# honeybee.net
KiCad netlist of a schematic drawn in EAGLE
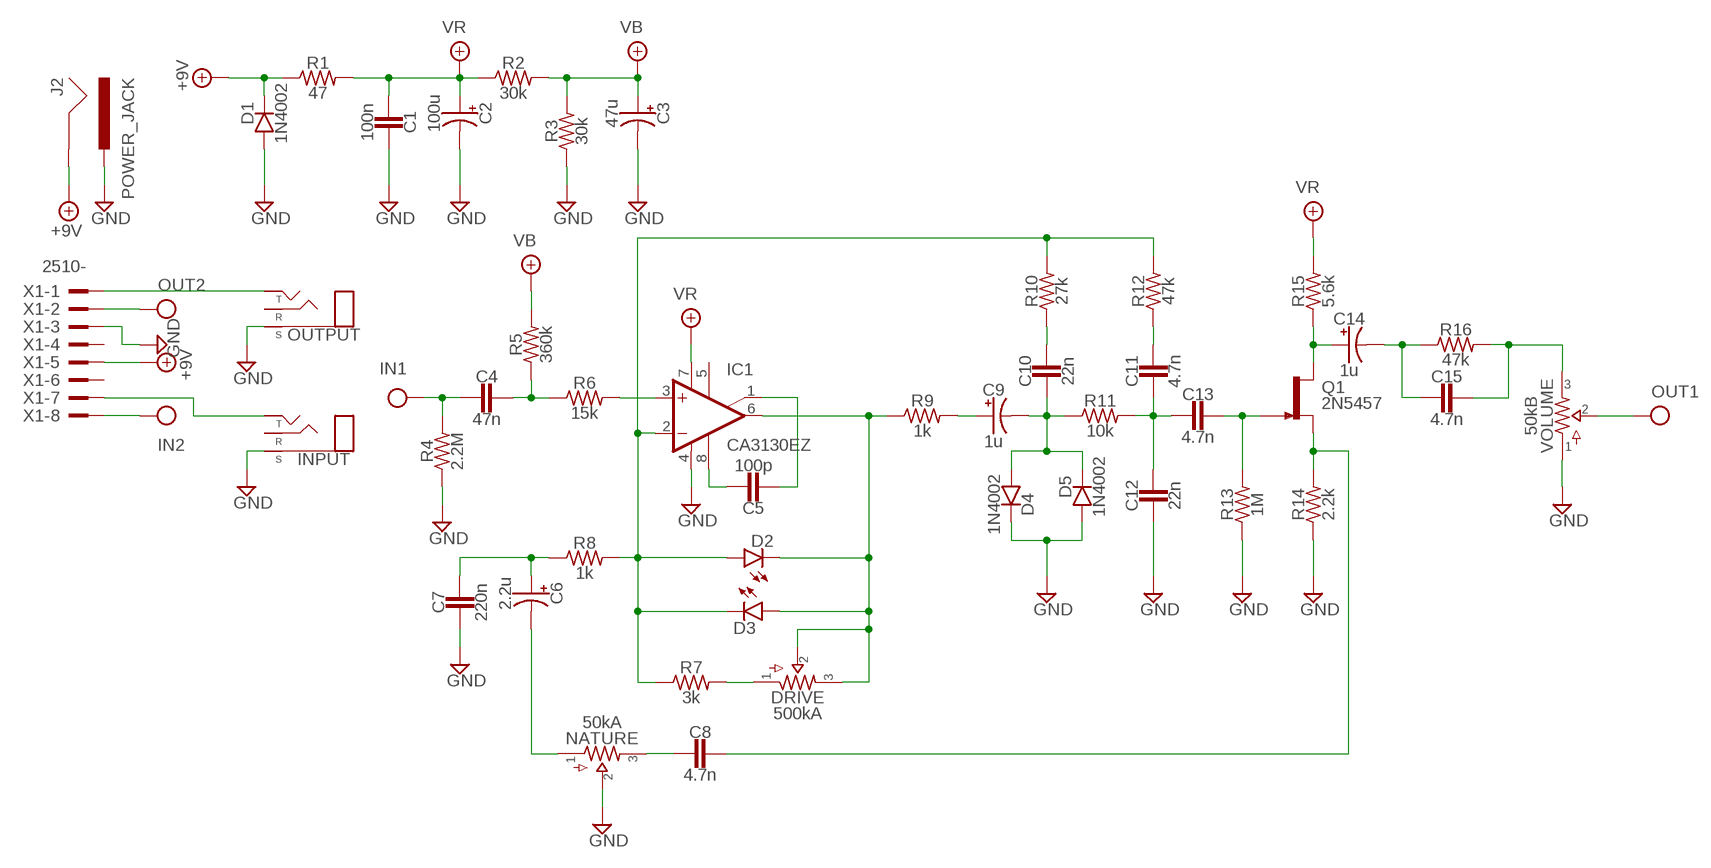
[diagram p0: schematic, sheet 1]

(export (version "E")
  (design (tool "Eeschema 10.0.6"))
  (components
    (comp (ref "C1")
      (value "100n")
      (footprint "eagle-import:050X030_025_2")
      (libsource (lib "eagle-import") (part "CER/FILM2"))
    )
    (comp (ref "C2")
      (value "100u")
      (footprint "eagle-import:040_020")
      (libsource (lib "eagle-import") (part "0400"))
    )
    (comp (ref "C3")
      (value "47u")
      (footprint "eagle-import:040_020")
      (libsource (lib "eagle-import") (part "0400"))
    )
    (comp (ref "C4")
      (value "47n")
      (footprint "eagle-import:BOX_SMALL")
      (libsource (lib "eagle-import") (part "CER/FILMBOX.1"))
    )
    (comp (ref "C5")
      (value "100p")
      (footprint "eagle-import:050X030_025_2")
      (libsource (lib "eagle-import") (part "CER/FILM2"))
    )
    (comp (ref "C6")
      (value "2.2u")
      (footprint "eagle-import:050_020")
      (libsource (lib "eagle-import") (part "0500"))
    )
    (comp (ref "C7")
      (value "220n")
      (footprint "eagle-import:BOX_SMALL")
      (libsource (lib "eagle-import") (part "CER/FILMBOX.1"))
    )
    (comp (ref "C8")
      (value "4.7n")
      (footprint "eagle-import:BOX_SMALL")
      (libsource (lib "eagle-import") (part "CER/FILMBOX.1"))
    )
    (comp (ref "C9")
      (value "1u")
      (footprint "eagle-import:040_020")
      (libsource (lib "eagle-import") (part "0400"))
    )
    (comp (ref "C10")
      (value "22n")
      (footprint "eagle-import:BOX_SMALL")
      (libsource (lib "eagle-import") (part "CER/FILMBOX.1"))
    )
    (comp (ref "C11")
      (value "4.7n")
      (footprint "eagle-import:BOX_SMALL")
      (libsource (lib "eagle-import") (part "CER/FILMBOX.1"))
    )
    (comp (ref "C12")
      (value "22n")
      (footprint "eagle-import:BOX_SMALL")
      (libsource (lib "eagle-import") (part "CER/FILMBOX.1"))
    )
    (comp (ref "C13")
      (value "4.7n")
      (footprint "eagle-import:BOX_SMALL")
      (libsource (lib "eagle-import") (part "CER/FILMBOX.1"))
    )
    (comp (ref "C14")
      (value "1u")
      (footprint "eagle-import:040_020")
      (libsource (lib "eagle-import") (part "0400"))
    )
    (comp (ref "C15")
      (value "4.7n")
      (footprint "eagle-import:BOX_SMALL")
      (libsource (lib "eagle-import") (part "CER/FILMBOX.1"))
    )
    (comp (ref "D1")
      (value "1N4002")
      (footprint "eagle-import:DO41-2")
      (libsource (lib "eagle-import") (part "DO41.2"))
    )
    (comp (ref "D2")
      (value "LED")
      (footprint "eagle-import:3MM_D")
      (libsource (lib "eagle-import") (part "LED"))
    )
    (comp (ref "D3")
      (value "LED")
      (footprint "eagle-import:3MM_D")
      (libsource (lib "eagle-import") (part "LED"))
    )
    (comp (ref "D4")
      (value "1N4002")
      (footprint "eagle-import:DO41-2")
      (libsource (lib "eagle-import") (part "DO41.2"))
    )
    (comp (ref "D5")
      (value "1N4002")
      (footprint "eagle-import:DO41-2")
      (libsource (lib "eagle-import") (part "DO41.2"))
    )
    (comp (ref "DRIVE")
      (value "500kA")
      (footprint "eagle-import:16MM")
      (libsource (lib "eagle-import") (part "POTS16MM"))
    )
    (comp (ref "IC1")
      (value "CA3130EZ")
      (footprint "eagle-import:DIL08")
      (libsource (lib "eagle-import") (part "CA3130N"))
    )
    (comp (ref "INPUT")
      (value "STEREONMJ")
      (footprint "eagle-import:NMJ6HCD2")
      (libsource (lib "eagle-import") (part "STEREONMJ"))
    )
    (comp (ref "J2")
      (value "POWER_JACK")
      (footprint "eagle-import:POWER_JACK_PTH")
      (libsource (lib "eagle-import") (part "POWER_JACK"))
    )
    (comp (ref "NATURE")
      (value "50kA")
      (footprint "eagle-import:16MM")
      (libsource (lib "eagle-import") (part "POTS16MM"))
    )
    (comp (ref "OUTPUT")
      (value "STEREONMJ")
      (footprint "eagle-import:NMJ6HCD2")
      (libsource (lib "eagle-import") (part "STEREONMJ"))
    )
    (comp (ref "Q1")
      (value "2N5457")
      (footprint "eagle-import:TO92-")
      (libsource (lib "eagle-import") (part "2N5457"))
    )
    (comp (ref "R1")
      (value "47")
      (footprint "eagle-import:R0207_3")
      (libsource (lib "eagle-import") (part "R_.3B"))
    )
    (comp (ref "R2")
      (value "30k")
      (footprint "eagle-import:R0207_3")
      (libsource (lib "eagle-import") (part "R_.3B"))
    )
    (comp (ref "R3")
      (value "30k")
      (footprint "eagle-import:R0207_3")
      (libsource (lib "eagle-import") (part "R_.3B"))
    )
    (comp (ref "R4")
      (value "2.2M")
      (footprint "eagle-import:R0207_3")
      (libsource (lib "eagle-import") (part "R_.3B"))
    )
    (comp (ref "R5")
      (value "360k")
      (footprint "eagle-import:R0207_3")
      (libsource (lib "eagle-import") (part "R_.3B"))
    )
    (comp (ref "R6")
      (value "15k")
      (footprint "eagle-import:R0207_3")
      (libsource (lib "eagle-import") (part "R_.3B"))
    )
    (comp (ref "R7")
      (value "3k")
      (footprint "eagle-import:R0207_3")
      (libsource (lib "eagle-import") (part "R_.3B"))
    )
    (comp (ref "R8")
      (value "1k")
      (footprint "eagle-import:R0207_3")
      (libsource (lib "eagle-import") (part "R_.3B"))
    )
    (comp (ref "R9")
      (value "1k")
      (footprint "eagle-import:R0207_3")
      (libsource (lib "eagle-import") (part "R_.3B"))
    )
    (comp (ref "R10")
      (value "27k")
      (footprint "eagle-import:R0207_3")
      (libsource (lib "eagle-import") (part "R_.3B"))
    )
    (comp (ref "R11")
      (value "10k")
      (footprint "eagle-import:R0207_3")
      (libsource (lib "eagle-import") (part "R_.3B"))
    )
    (comp (ref "R12")
      (value "47k")
      (footprint "eagle-import:R0207_3")
      (libsource (lib "eagle-import") (part "R_.3B"))
    )
    (comp (ref "R13")
      (value "1M")
      (footprint "eagle-import:R0207_3")
      (libsource (lib "eagle-import") (part "R_.3B"))
    )
    (comp (ref "R14")
      (value "2.2k")
      (footprint "eagle-import:R0207_3")
      (libsource (lib "eagle-import") (part "R_.3B"))
    )
    (comp (ref "R15")
      (value "5.6k")
      (footprint "eagle-import:R0207_3")
      (libsource (lib "eagle-import") (part "R_.3B"))
    )
    (comp (ref "R16")
      (value "47k")
      (footprint "eagle-import:R0207_3")
      (libsource (lib "eagle-import") (part "R_.3B"))
    )
    (comp (ref "VOLUME")
      (value "50kB")
      (footprint "eagle-import:16MM")
      (libsource (lib "eagle-import") (part "POTS16MM"))
    )
    (comp (ref "X1")
      (value "2510-")
      (footprint "eagle-import:PAK100_2500-10")
      (fields (field (name "MF") "3M") (field (name "MPN") "2510-6002UB"))
      (libsource (lib "eagle-import") (part "2510-"))
    )
  )
  (nets
    (net (code "1") (name "+9V") (class "Default")
      (node (ref "D1") (pin "C") (pinfunction "C_C") (pintype "passive"))
      (node (ref "J2") (pin "GND") (pinfunction "GND_GND") (pintype "bidirectional"))
      (node (ref "R1") (pin "1") (pinfunction "1_1") (pintype "passive"))
      (node (ref "X1") (pin "5") (pinfunction "KL_5") (pintype "passive"))
    )
    (net (code "2") (name "GND") (class "Default")
      (node (ref "C1") (pin "1") (pinfunction "1_1") (pintype "passive"))
      (node (ref "C12") (pin "2") (pinfunction "2_2") (pintype "passive"))
      (node (ref "C2") (pin "-") (pinfunction "-_-") (pintype "passive"))
      (node (ref "C3") (pin "-") (pinfunction "-_-") (pintype "passive"))
      (node (ref "C7") (pin "2") (pinfunction "2_2") (pintype "passive"))
      (node (ref "D1") (pin "A") (pinfunction "A_A") (pintype "passive"))
      (node (ref "D4") (pin "C") (pinfunction "C_C") (pintype "passive"))
      (node (ref "D5") (pin "A") (pinfunction "A_A") (pintype "passive"))
      (node (ref "IC1") (pin "4") (pinfunction "V-_4") (pintype "power_in"))
      (node (ref "INPUT") (pin "S") (pinfunction "S_S") (pintype "passive"))
      (node (ref "J2") (pin "PWR") (pinfunction "PWR_PWR") (pintype "bidirectional"))
      (node (ref "NATURE") (pin "2") (pinfunction "2_2") (pintype "passive"))
      (node (ref "OUTPUT") (pin "S") (pinfunction "S_S") (pintype "passive"))
      (node (ref "R13") (pin "1") (pinfunction "1_1") (pintype "passive"))
      (node (ref "R14") (pin "1") (pinfunction "1_1") (pintype "passive"))
      (node (ref "R3") (pin "1") (pinfunction "1_1") (pintype "passive"))
      (node (ref "R4") (pin "1") (pinfunction "1_1") (pintype "passive"))
      (node (ref "VOLUME") (pin "1") (pinfunction "1_1") (pintype "passive"))
      (node (ref "X1") (pin "3") (pinfunction "KL_3") (pintype "passive"))
    )
    (net (code "3") (name "IN") (class "Default")
      (node (ref "C4") (pin "2") (pinfunction "2_2") (pintype "passive"))
      (node (ref "R4") (pin "2") (pinfunction "2_2") (pintype "passive"))
      (node (ref "X1") (pin "8") (pinfunction "KL_8") (pintype "passive"))
    )
    (net (code "4") (name "Net-(C4-Pad1)") (class "Default")
      (node (ref "C4") (pin "1") (pinfunction "1_1") (pintype "passive"))
      (node (ref "R5") (pin "1") (pinfunction "1_1") (pintype "passive"))
      (node (ref "R6") (pin "1") (pinfunction "1_1") (pintype "passive"))
    )
    (net (code "5") (name "Net-(C6-Pad+)") (class "Default")
      (node (ref "C6") (pin "+") (pinfunction "+_+") (pintype "passive"))
      (node (ref "C7") (pin "1") (pinfunction "1_1") (pintype "passive"))
      (node (ref "R8") (pin "1") (pinfunction "1_1") (pintype "passive"))
    )
    (net (code "6") (name "Net-(C6-Pad-)") (class "Default")
      (node (ref "C6") (pin "-") (pinfunction "-_-") (pintype "passive"))
      (node (ref "NATURE") (pin "1") (pinfunction "1_1") (pintype "passive"))
    )
    (net (code "7") (name "Net-(C8-Pad2)") (class "Default")
      (node (ref "C8") (pin "2") (pinfunction "2_2") (pintype "passive"))
      (node (ref "NATURE") (pin "3") (pinfunction "3_3") (pintype "passive"))
    )
    (net (code "8") (name "Net-(C9-Pad+)") (class "Default")
      (node (ref "C9") (pin "+") (pinfunction "+_+") (pintype "passive"))
      (node (ref "R9") (pin "2") (pinfunction "2_2") (pintype "passive"))
    )
    (net (code "9") (name "Net-(C10-Pad1)") (class "Default")
      (node (ref "C10") (pin "1") (pinfunction "1_1") (pintype "passive"))
      (node (ref "R10") (pin "1") (pinfunction "1_1") (pintype "passive"))
    )
    (net (code "10") (name "Net-(C10-Pad2)") (class "Default")
      (node (ref "C10") (pin "2") (pinfunction "2_2") (pintype "passive"))
      (node (ref "C9") (pin "-") (pinfunction "-_-") (pintype "passive"))
      (node (ref "D4") (pin "A") (pinfunction "A_A") (pintype "passive"))
      (node (ref "D5") (pin "C") (pinfunction "C_C") (pintype "passive"))
      (node (ref "R11") (pin "1") (pinfunction "1_1") (pintype "passive"))
    )
    (net (code "11") (name "Net-(C11-Pad1)") (class "Default")
      (node (ref "C11") (pin "1") (pinfunction "1_1") (pintype "passive"))
      (node (ref "R12") (pin "1") (pinfunction "1_1") (pintype "passive"))
    )
    (net (code "12") (name "Net-(C11-Pad2)") (class "Default")
      (node (ref "C11") (pin "2") (pinfunction "2_2") (pintype "passive"))
      (node (ref "C12") (pin "1") (pinfunction "1_1") (pintype "passive"))
      (node (ref "C13") (pin "2") (pinfunction "2_2") (pintype "passive"))
      (node (ref "R11") (pin "2") (pinfunction "2_2") (pintype "passive"))
    )
    (net (code "13") (name "Net-(C14-Pad-)") (class "Default")
      (node (ref "C14") (pin "-") (pinfunction "-_-") (pintype "passive"))
      (node (ref "C15") (pin "2") (pinfunction "2_2") (pintype "passive"))
      (node (ref "R16") (pin "1") (pinfunction "1_1") (pintype "passive"))
    )
    (net (code "14") (name "Net-(C15-Pad1)") (class "Default")
      (node (ref "C15") (pin "1") (pinfunction "1_1") (pintype "passive"))
      (node (ref "R16") (pin "2") (pinfunction "2_2") (pintype "passive"))
      (node (ref "VOLUME") (pin "3") (pinfunction "3_3") (pintype "passive"))
    )
    (net (code "15") (name "Net-(D2-A)") (class "Default")
      (node (ref "D2") (pin "ANODE") (pinfunction "A_ANODE") (pintype "passive"))
      (node (ref "D3") (pin "P$1") (pinfunction "C_P$1") (pintype "passive"))
      (node (ref "IC1") (pin "2") (pinfunction "-IN_2") (pintype "input"))
      (node (ref "R10") (pin "2") (pinfunction "2_2") (pintype "passive"))
      (node (ref "R12") (pin "2") (pinfunction "2_2") (pintype "passive"))
      (node (ref "R7") (pin "1") (pinfunction "1_1") (pintype "passive"))
      (node (ref "R8") (pin "2") (pinfunction "2_2") (pintype "passive"))
    )
    (net (code "16") (name "Net-(D2-C)") (class "Default")
      (node (ref "D2") (pin "P$1") (pinfunction "C_P$1") (pintype "passive"))
      (node (ref "D3") (pin "ANODE") (pinfunction "A_ANODE") (pintype "passive"))
      (node (ref "DRIVE") (pin "2") (pinfunction "2_2") (pintype "passive"))
      (node (ref "DRIVE") (pin "3") (pinfunction "3_3") (pintype "passive"))
      (node (ref "IC1") (pin "6") (pinfunction "OUT_6") (pintype "output"))
      (node (ref "R9") (pin "1") (pinfunction "1_1") (pintype "passive"))
    )
    (net (code "17") (name "Net-(DRIVE-Pad1)") (class "Default")
      (node (ref "DRIVE") (pin "1") (pinfunction "1_1") (pintype "passive"))
      (node (ref "R7") (pin "2") (pinfunction "2_2") (pintype "passive"))
    )
    (net (code "18") (name "Net-(IC1-+IN)") (class "Default")
      (node (ref "IC1") (pin "3") (pinfunction "+IN_3") (pintype "input"))
      (node (ref "R6") (pin "2") (pinfunction "2_2") (pintype "passive"))
    )
    (net (code "19") (name "Net-(IC1-CMP)") (class "Default")
      (node (ref "C5") (pin "1") (pinfunction "1_1") (pintype "passive"))
      (node (ref "IC1") (pin "8") (pinfunction "CMP_8") (pintype "passive"))
    )
    (net (code "20") (name "Net-(IC1-ON{slash}CMP)") (class "Default")
      (node (ref "C5") (pin "2") (pinfunction "2_2") (pintype "passive"))
      (node (ref "IC1") (pin "1") (pinfunction "ON/CMP_1") (pintype "passive"))
    )
    (net (code "21") (name "Net-(Q1-D)") (class "Default")
      (node (ref "C14") (pin "+") (pinfunction "+_+") (pintype "passive"))
      (node (ref "Q1") (pin "3") (pinfunction "D_3") (pintype "passive"))
      (node (ref "R15") (pin "1") (pinfunction "1_1") (pintype "passive"))
    )
    (net (code "22") (name "Net-(Q1-G)") (class "Default")
      (node (ref "C13") (pin "1") (pinfunction "1_1") (pintype "passive"))
      (node (ref "Q1") (pin "1") (pinfunction "G_1") (pintype "passive"))
      (node (ref "R13") (pin "2") (pinfunction "2_2") (pintype "passive"))
    )
    (net (code "23") (name "Net-(Q1-S)") (class "Default")
      (node (ref "C8") (pin "1") (pinfunction "1_1") (pintype "passive"))
      (node (ref "Q1") (pin "2") (pinfunction "S_2") (pintype "passive"))
      (node (ref "R14") (pin "2") (pinfunction "2_2") (pintype "passive"))
    )
    (net (code "24") (name "Net-(X1A-KL)") (class "Default")
      (node (ref "OUTPUT") (pin "T") (pinfunction "T_T") (pintype "passive"))
      (node (ref "X1") (pin "1") (pinfunction "KL_1") (pintype "passive"))
    )
    (net (code "25") (name "Net-(X1G-KL)") (class "Default")
      (node (ref "INPUT") (pin "T") (pinfunction "T_T") (pintype "passive"))
      (node (ref "X1") (pin "7") (pinfunction "KL_7") (pintype "passive"))
    )
    (net (code "26") (name "OUT") (class "Default")
      (node (ref "VOLUME") (pin "2") (pinfunction "2_2") (pintype "passive"))
      (node (ref "X1") (pin "2") (pinfunction "KL_2") (pintype "passive"))
    )
    (net (code "27") (name "VB") (class "Default")
      (node (ref "C3") (pin "+") (pinfunction "+_+") (pintype "passive"))
      (node (ref "R2") (pin "2") (pinfunction "2_2") (pintype "passive"))
      (node (ref "R3") (pin "2") (pinfunction "2_2") (pintype "passive"))
      (node (ref "R5") (pin "2") (pinfunction "2_2") (pintype "passive"))
    )
    (net (code "28") (name "VR") (class "Default")
      (node (ref "C1") (pin "2") (pinfunction "2_2") (pintype "passive"))
      (node (ref "C2") (pin "+") (pinfunction "+_+") (pintype "passive"))
      (node (ref "IC1") (pin "7") (pinfunction "V+_7") (pintype "power_in"))
      (node (ref "R1") (pin "2") (pinfunction "2_2") (pintype "passive"))
      (node (ref "R15") (pin "2") (pinfunction "2_2") (pintype "passive"))
      (node (ref "R2") (pin "1") (pinfunction "1_1") (pintype "passive"))
    )
    (net (code "29") (name "unconnected-(IC1-ON-Pad5)") (class "Default")
      (node (ref "IC1") (pin "5") (pinfunction "ON_5") (pintype "passive"))
    )
    (net (code "30") (name "unconnected-(INPUT-PadR)") (class "Default")
      (node (ref "INPUT") (pin "R") (pinfunction "R_R") (pintype "passive"))
    )
    (net (code "31") (name "unconnected-(OUTPUT-PadR)") (class "Default")
      (node (ref "OUTPUT") (pin "R") (pinfunction "R_R") (pintype "passive"))
    )
    (net (code "32") (name "unconnected-(X1D-KL-Pad4)") (class "Default")
      (node (ref "X1") (pin "4") (pinfunction "KL_4") (pintype "passive"))
    )
    (net (code "33") (name "unconnected-(X1F-KL-Pad6)") (class "Default")
      (node (ref "X1") (pin "6") (pinfunction "KL_6") (pintype "passive"))
    )
  )
)
